# Power-Tree.net
KiCad netlist of a schematic drawn in Altium Designer
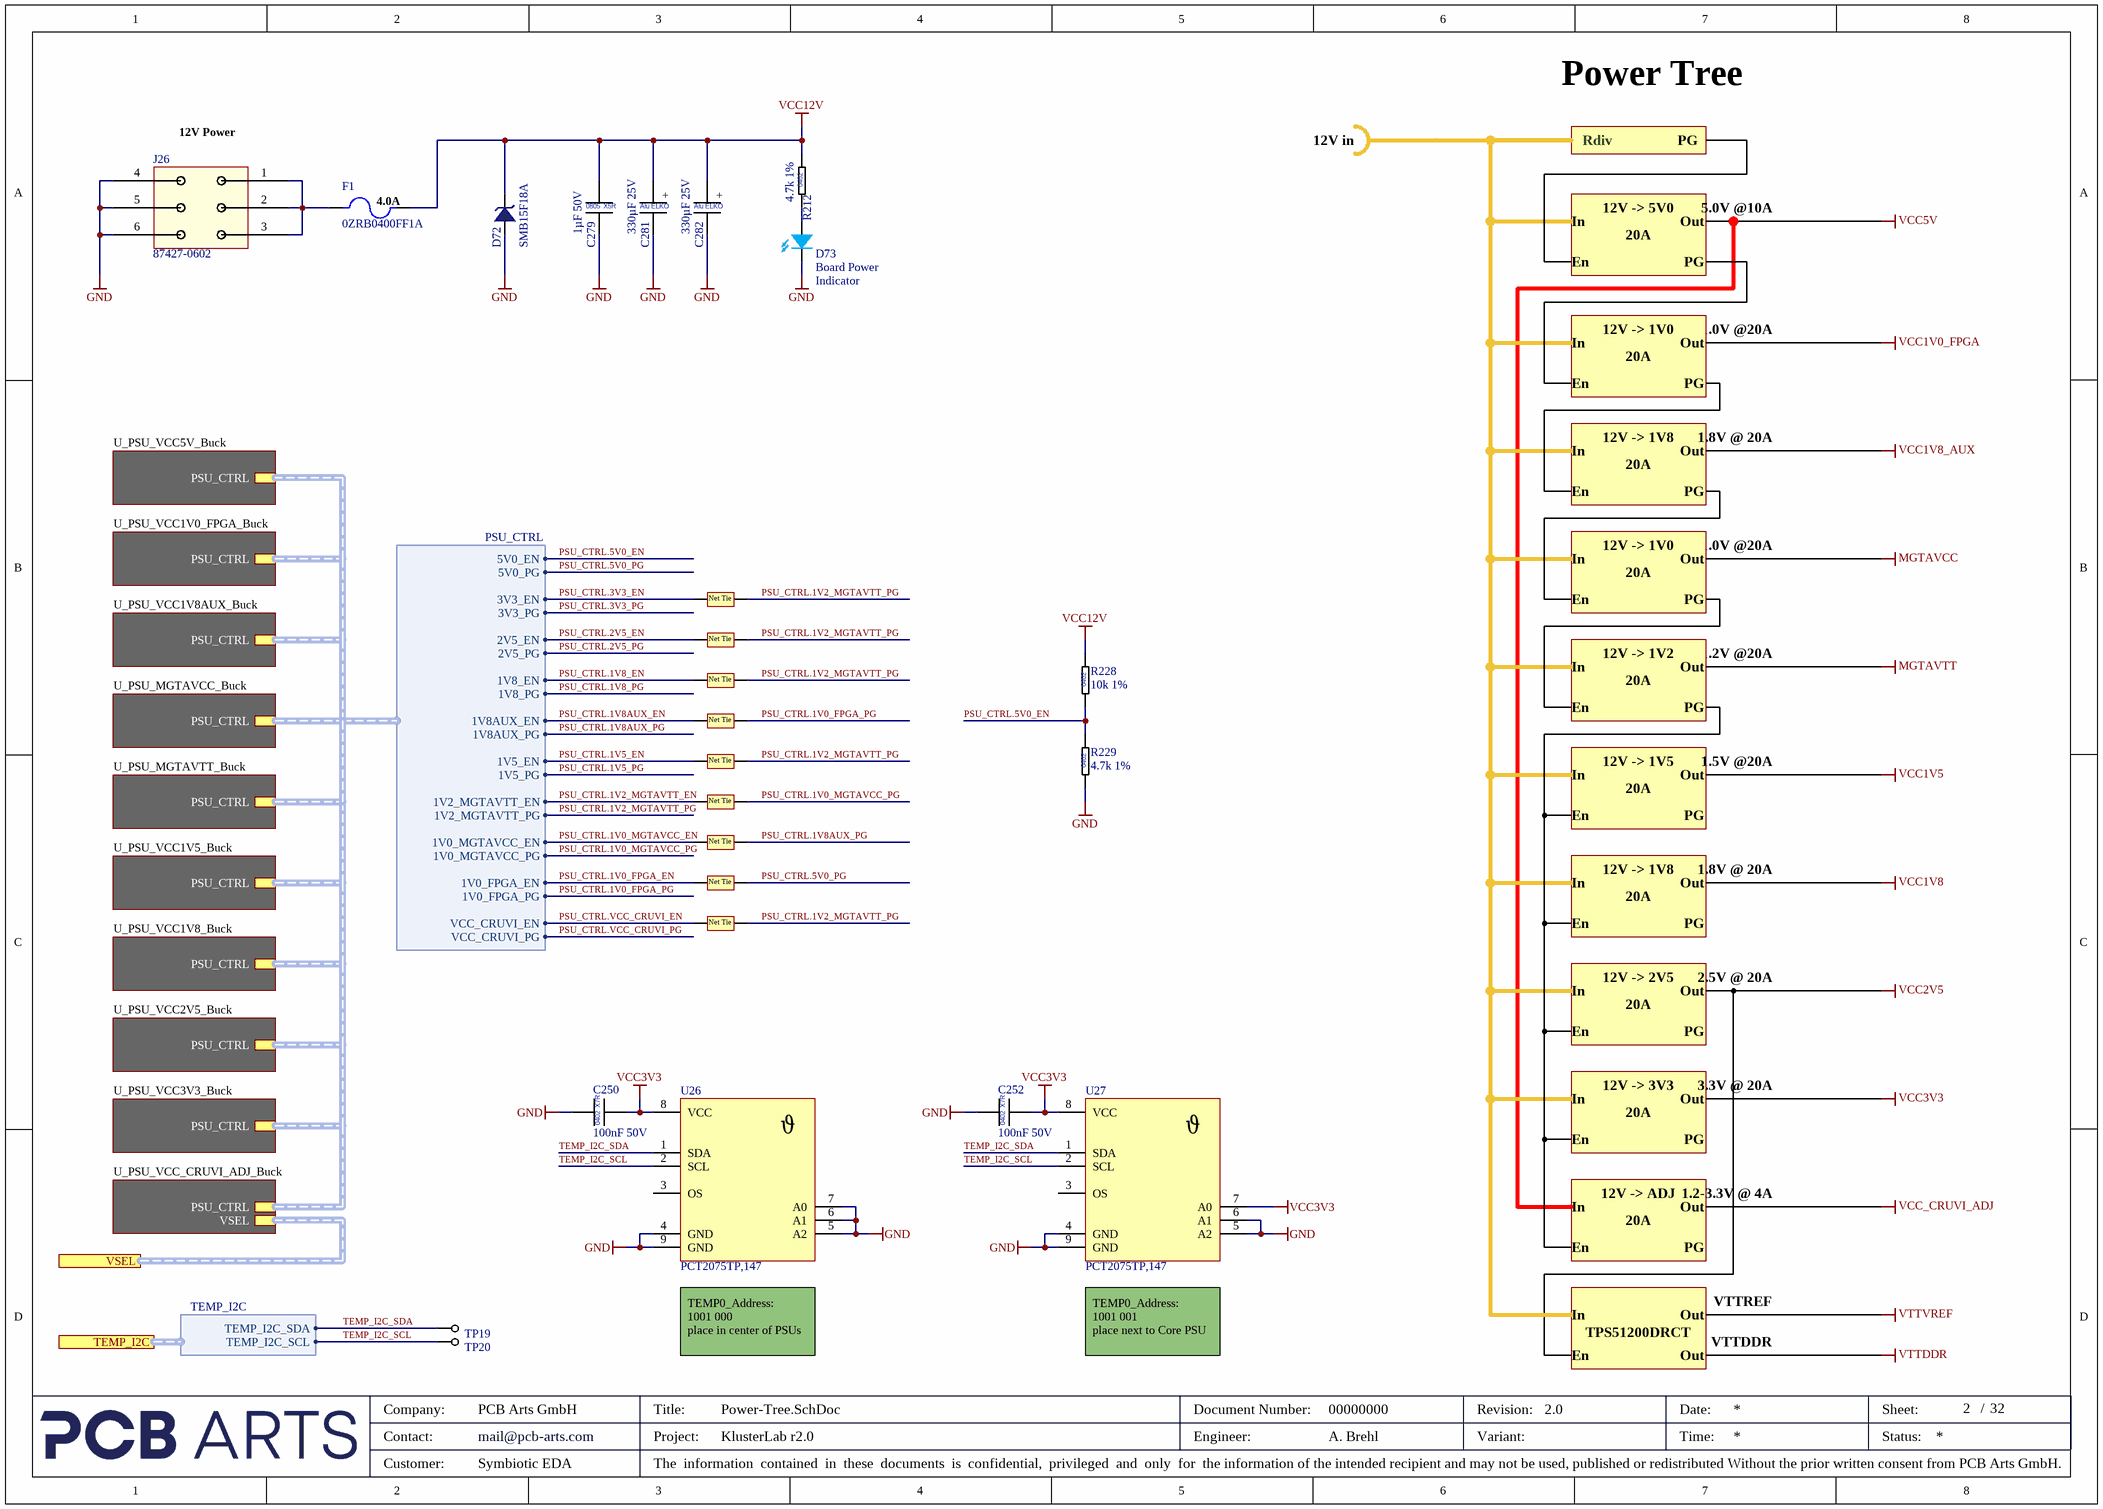
[diagram p0: Power-Tree.SchDoc]

(export (version "E")
  (design (tool "Eeschema 10.0.6"))
  (components
    (comp (ref "C250")
      (value "100nF 50V")
      (footprint "Cap:CAP_0402_L")
      (description "Multilayer Ceramic Capacitors MLCC - SMD/SMT 0402 50VDC")
      (libsource (lib "Cap") (part "CAP_0402_100nF_50V"))
    )
    (comp (ref "C252")
      (value "100nF 50V")
      (footprint "Cap:CAP_0402_L")
      (description "Multilayer Ceramic Capacitors MLCC - SMD/SMT 0402 50VDC")
      (libsource (lib "Cap") (part "CAP_0402_100nF_50V"))
    )
    (comp (ref "C279")
      (value "1µF 50V")
      (footprint "Cap:CAP_0805")
      (description "Multilayer Ceramic Capacitors MLCC - SMD/SMT 0805 50VDC")
      (libsource (lib "Cap") (part "CAP_0805_1µF_50V"))
    )
    (comp (ref "C281")
      (value "330µF 25V")
      (footprint "Cap:WCAP-PTG5_D10H12.5")
      (description "Organische Polymer-Aluminiumkondensatoren 330uF 25 Volts 20% AEC-Q200")
      (libsource (lib "Cap") (part "CAP_D10L12.5_330µF_25V"))
    )
    (comp (ref "C282")
      (value "330µF 25V")
      (footprint "Cap:WCAP-PTG5_D10H12.5")
      (description "Organische Polymer-Aluminiumkondensatoren 330uF 25 Volts 20% AEC-Q200")
      (libsource (lib "Cap") (part "CAP_D10L12.5_330µF_25V"))
    )
    (comp (ref "D72")
      (value "SMB15F18A")
      (footprint "Protec:DO221-AA")
      (description "ESD-Entstörer/TVS-Dioden 1500 W, 18 V TVS")
      (libsource (lib "Protec") (part "SMB15F18A_ESD-Entstörer/TVS-Dioden 1500 W, 18 V TVS"))
    )
    (comp (ref "D73")
      (value "LTST-S270TBKT")
      (footprint "Active:LED-0603 Sideview")
      (description "BLUE  0603 Light Emitting Diode")
      (libsource (lib "Active") (part "LED 0603 Blue Sideview"))
    )
    (comp (ref "F1")
      (value "0ZRB0400FF1A")
      (footprint "Protec:0ZRB0400FF")
      (description "Rückstellbare Sicherung 4.0A, 30V")
      (libsource (lib "Protec") (part "0ZRB0400FF1A_Rückstellbare Sicherung 4.0A, 30V"))
    )
    (comp (ref "J26")
      (value "87427-0602")
      (footprint "Molex 87427-0602")
      (description "Mini-Fit Jr. Right angle Header, 4.20mm Pitch, Dual Row, 6 Circuits")
      (libsource (lib "Conn") (part "87427-0602_Mini-Fit Jr. Right angle Header, 4.20mm Pitch, Dual Row, 6 Circuits"))
    )
    (comp (ref "NT1")
      (value "Net Tie")
      (footprint "Passive:Net Tie-0.3")
      (libsource (lib "Passive") (part "Net Tie"))
    )
    (comp (ref "NT2")
      (value "Net Tie")
      (footprint "Passive:Net Tie-0.3")
      (libsource (lib "Passive") (part "Net Tie"))
    )
    (comp (ref "NT3")
      (value "Net Tie")
      (footprint "Passive:Net Tie-0.3")
      (libsource (lib "Passive") (part "Net Tie"))
    )
    (comp (ref "NT4")
      (value "Net Tie")
      (footprint "Passive:Net Tie-0.3")
      (libsource (lib "Passive") (part "Net Tie"))
    )
    (comp (ref "NT5")
      (value "Net Tie")
      (footprint "Passive:Net Tie-0.3")
      (libsource (lib "Passive") (part "Net Tie"))
    )
    (comp (ref "NT6")
      (value "Net Tie")
      (footprint "Passive:Net Tie-0.3")
      (libsource (lib "Passive") (part "Net Tie"))
    )
    (comp (ref "NT7")
      (value "Net Tie")
      (footprint "Passive:Net Tie-0.3")
      (libsource (lib "Passive") (part "Net Tie"))
    )
    (comp (ref "NT8")
      (value "Net Tie")
      (footprint "Passive:Net Tie-0.3")
      (libsource (lib "Passive") (part "Net Tie"))
    )
    (comp (ref "NT9")
      (value "Net Tie")
      (footprint "Passive:Net Tie-0.3")
      (libsource (lib "Passive") (part "Net Tie"))
    )
    (comp (ref "R212")
      (value "4.7k 1%")
      (footprint "Res:RES_0402_L")
      (description "Thick Film Resistors - SMD 4.7kOhm 1%")
      (libsource (lib "Res") (part "RES_0402_4.7k_1%"))
    )
    (comp (ref "R228")
      (value "10k 1%")
      (footprint "Res:RES_0402_L")
      (description "Thick Film Resistors - SMD 10kOhm 1%")
      (libsource (lib "Res") (part "RES_0402_10k_1%"))
    )
    (comp (ref "R229")
      (value "4.7k 1%")
      (footprint "Res:RES_0402_L")
      (description "Thick Film Resistors - SMD 4.7kOhm 1%")
      (libsource (lib "Res") (part "RES_0402_4.7k_1%"))
    )
    (comp (ref "TP19")
      (value "Testpoint")
      (footprint "Electro_mech:Testpoint 0.8mm")
      (description "Testpoint 0.8mm")
      (libsource (lib "Electro_Mech") (part "Testpoint 0.8mm"))
    )
    (comp (ref "TP20")
      (value "Testpoint")
      (footprint "Electro_mech:Testpoint 0.8mm")
      (description "Testpoint 0.8mm")
      (libsource (lib "Electro_Mech") (part "Testpoint 0.8mm"))
    )
    (comp (ref "U26")
      (value "PCT2075TP,147")
      (footprint "Active:SOT1069-2 (HWSON8)")
      (description "Digital Temp Sensor I2C")
      (libsource (lib "Active") (part "PCT2075TP,147_Digital Temp Sensor I2C"))
    )
    (comp (ref "U27")
      (value "PCT2075TP,147")
      (footprint "Active:SOT1069-2 (HWSON8)")
      (description "Digital Temp Sensor I2C")
      (libsource (lib "Active") (part "PCT2075TP,147_Digital Temp Sensor I2C"))
    )
  )
  (nets
    (net (code "4") (name "/PSU_CTRL.1V0_FPGA_EN") (class "Default")
      (node (ref "NT8") (pin "1") (pinfunction "1_1") (pintype "passive"))
    )
    (net (code "5") (name "/PSU_CTRL.1V0_FPGA_PG") (class "Default")
      (node (ref "NT4") (pin "2") (pinfunction "2_2") (pintype "passive"))
    )
    (net (code "6") (name "/PSU_CTRL.1V0_MGTAVCC_EN") (class "Default")
      (node (ref "NT7") (pin "1") (pinfunction "1_1") (pintype "passive"))
    )
    (net (code "7") (name "/PSU_CTRL.1V0_MGTAVCC_PG") (class "Default")
      (node (ref "NT6") (pin "2") (pinfunction "2_2") (pintype "passive"))
    )
    (net (code "8") (name "/PSU_CTRL.1V2_MGTAVTT_EN") (class "Default")
      (node (ref "NT6") (pin "1") (pinfunction "1_1") (pintype "passive"))
    )
    (net (code "9") (name "/PSU_CTRL.1V2_MGTAVTT_PG") (class "Default")
      (node (ref "NT1") (pin "2") (pinfunction "2_2") (pintype "passive"))
      (node (ref "NT2") (pin "2") (pinfunction "2_2") (pintype "passive"))
      (node (ref "NT3") (pin "2") (pinfunction "2_2") (pintype "passive"))
      (node (ref "NT5") (pin "2") (pinfunction "2_2") (pintype "passive"))
      (node (ref "NT9") (pin "2") (pinfunction "2_2") (pintype "passive"))
    )
    (net (code "10") (name "/PSU_CTRL.1V5_EN") (class "Default")
      (node (ref "NT5") (pin "1") (pinfunction "1_1") (pintype "passive"))
    )
    (net (code "12") (name "/PSU_CTRL.1V8AUX_EN") (class "Default")
      (node (ref "NT4") (pin "1") (pinfunction "1_1") (pintype "passive"))
    )
    (net (code "13") (name "/PSU_CTRL.1V8AUX_PG") (class "Default")
      (node (ref "NT7") (pin "2") (pinfunction "2_2") (pintype "passive"))
    )
    (net (code "14") (name "/PSU_CTRL.1V8_EN") (class "Default")
      (node (ref "NT3") (pin "1") (pinfunction "1_1") (pintype "passive"))
    )
    (net (code "16") (name "/PSU_CTRL.2V5_EN") (class "Default")
      (node (ref "NT2") (pin "1") (pinfunction "1_1") (pintype "passive"))
    )
    (net (code "18") (name "/PSU_CTRL.3V3_EN") (class "Default")
      (node (ref "NT1") (pin "1") (pinfunction "1_1") (pintype "passive"))
    )
    (net (code "20") (name "/PSU_CTRL.5V0_EN") (class "Default")
      (node (ref "R228") (pin "1") (pinfunction "1_1") (pintype "passive"))
      (node (ref "R229") (pin "2") (pinfunction "2_2") (pintype "passive"))
    )
    (net (code "21") (name "/PSU_CTRL.5V0_PG") (class "Default")
      (node (ref "NT8") (pin "2") (pinfunction "2_2") (pintype "passive"))
    )
    (net (code "22") (name "/PSU_CTRL.VCC_CRUVI_EN") (class "Default")
      (node (ref "NT9") (pin "1") (pinfunction "1_1") (pintype "passive"))
    )
    (net (code "24") (name "/TEMP_I2C_SCL") (class "Default")
      (node (ref "TP20") (pin "1") (pinfunction "GND_1") (pintype "passive"))
      (node (ref "U26") (pin "2") (pinfunction "SCL_2") (pintype "passive"))
      (node (ref "U27") (pin "2") (pinfunction "SCL_2") (pintype "passive"))
    )
    (net (code "25") (name "/TEMP_I2C_SDA") (class "Default")
      (node (ref "TP19") (pin "1") (pinfunction "GND_1") (pintype "passive"))
      (node (ref "U26") (pin "1") (pinfunction "SDA_1") (pintype "passive"))
      (node (ref "U27") (pin "1") (pinfunction "SDA_1") (pintype "passive"))
    )
    (net (code "29") (name "GND") (class "Default")
      (node (ref "C250") (pin "1") (pinfunction "1_1") (pintype "passive"))
      (node (ref "C252") (pin "1") (pinfunction "1_1") (pintype "passive"))
      (node (ref "C279") (pin "2") (pinfunction "2_2") (pintype "passive"))
      (node (ref "C281") (pin "2") (pinfunction "2_2") (pintype "passive"))
      (node (ref "C282") (pin "2") (pinfunction "2_2") (pintype "passive"))
      (node (ref "D72") (pin "2") (pinfunction "2_2") (pintype "passive"))
      (node (ref "D73") (pin "1") (pinfunction "1_1") (pintype "passive"))
      (node (ref "J26") (pin "4") (pinfunction "4_4") (pintype "passive"))
      (node (ref "J26") (pin "5") (pinfunction "5_5") (pintype "passive"))
      (node (ref "J26") (pin "6") (pinfunction "6_6") (pintype "passive"))
      (node (ref "R229") (pin "1") (pinfunction "1_1") (pintype "passive"))
      (node (ref "U26") (pin "4") (pinfunction "GND_4") (pintype "passive"))
      (node (ref "U26") (pin "5") (pinfunction "A2_5") (pintype "passive"))
      (node (ref "U26") (pin "6") (pinfunction "A1_6") (pintype "passive"))
      (node (ref "U26") (pin "7") (pinfunction "A0_7") (pintype "passive"))
      (node (ref "U26") (pin "9") (pinfunction "GND_9") (pintype "passive"))
      (node (ref "U27") (pin "4") (pinfunction "GND_4") (pintype "passive"))
      (node (ref "U27") (pin "5") (pinfunction "A2_5") (pintype "passive"))
      (node (ref "U27") (pin "6") (pinfunction "A1_6") (pintype "passive"))
      (node (ref "U27") (pin "9") (pinfunction "GND_9") (pintype "passive"))
    )
    (net (code "30") (name "Net-(D73-Pad2)") (class "Default")
      (node (ref "D73") (pin "2") (pinfunction "2_2") (pintype "passive"))
      (node (ref "R212") (pin "1") (pinfunction "1_1") (pintype "passive"))
    )
    (net (code "31") (name "Net-(F1-Pad1)") (class "Default")
      (node (ref "F1") (pin "1") (pinfunction "1_1") (pintype "passive"))
      (node (ref "J26") (pin "1") (pinfunction "1_1") (pintype "passive"))
      (node (ref "J26") (pin "2") (pinfunction "2_2") (pintype "passive"))
      (node (ref "J26") (pin "3") (pinfunction "3_3") (pintype "passive"))
    )
    (net (code "32") (name "VCC3V3") (class "Default")
      (node (ref "C250") (pin "2") (pinfunction "2_2") (pintype "passive"))
      (node (ref "C252") (pin "2") (pinfunction "2_2") (pintype "passive"))
      (node (ref "U26") (pin "8") (pinfunction "VCC_8") (pintype "passive"))
      (node (ref "U27") (pin "7") (pinfunction "A0_7") (pintype "passive"))
      (node (ref "U27") (pin "8") (pinfunction "VCC_8") (pintype "passive"))
    )
    (net (code "33") (name "VCC12V") (class "Default")
      (node (ref "C279") (pin "1") (pinfunction "1_1") (pintype "passive"))
      (node (ref "C281") (pin "1") (pinfunction "1_1") (pintype "passive"))
      (node (ref "C282") (pin "1") (pinfunction "1_1") (pintype "passive"))
      (node (ref "D72") (pin "1") (pinfunction "1_1") (pintype "passive"))
      (node (ref "F1") (pin "2") (pinfunction "2_2") (pintype "passive"))
      (node (ref "R212") (pin "2") (pinfunction "2_2") (pintype "passive"))
      (node (ref "R228") (pin "2") (pinfunction "2_2") (pintype "passive"))
    )
    (net (code "34") (name "unconnected-(U26-OS-Pad3)") (class "Default")
      (node (ref "U26") (pin "3") (pinfunction "OS_3") (pintype "passive"))
    )
    (net (code "35") (name "unconnected-(U27-OS-Pad3)") (class "Default")
      (node (ref "U27") (pin "3") (pinfunction "OS_3") (pintype "passive"))
    )
  )
)
